# CmosTest20231115V3.net
KiCad netlist of a schematic drawn in Altium Designer
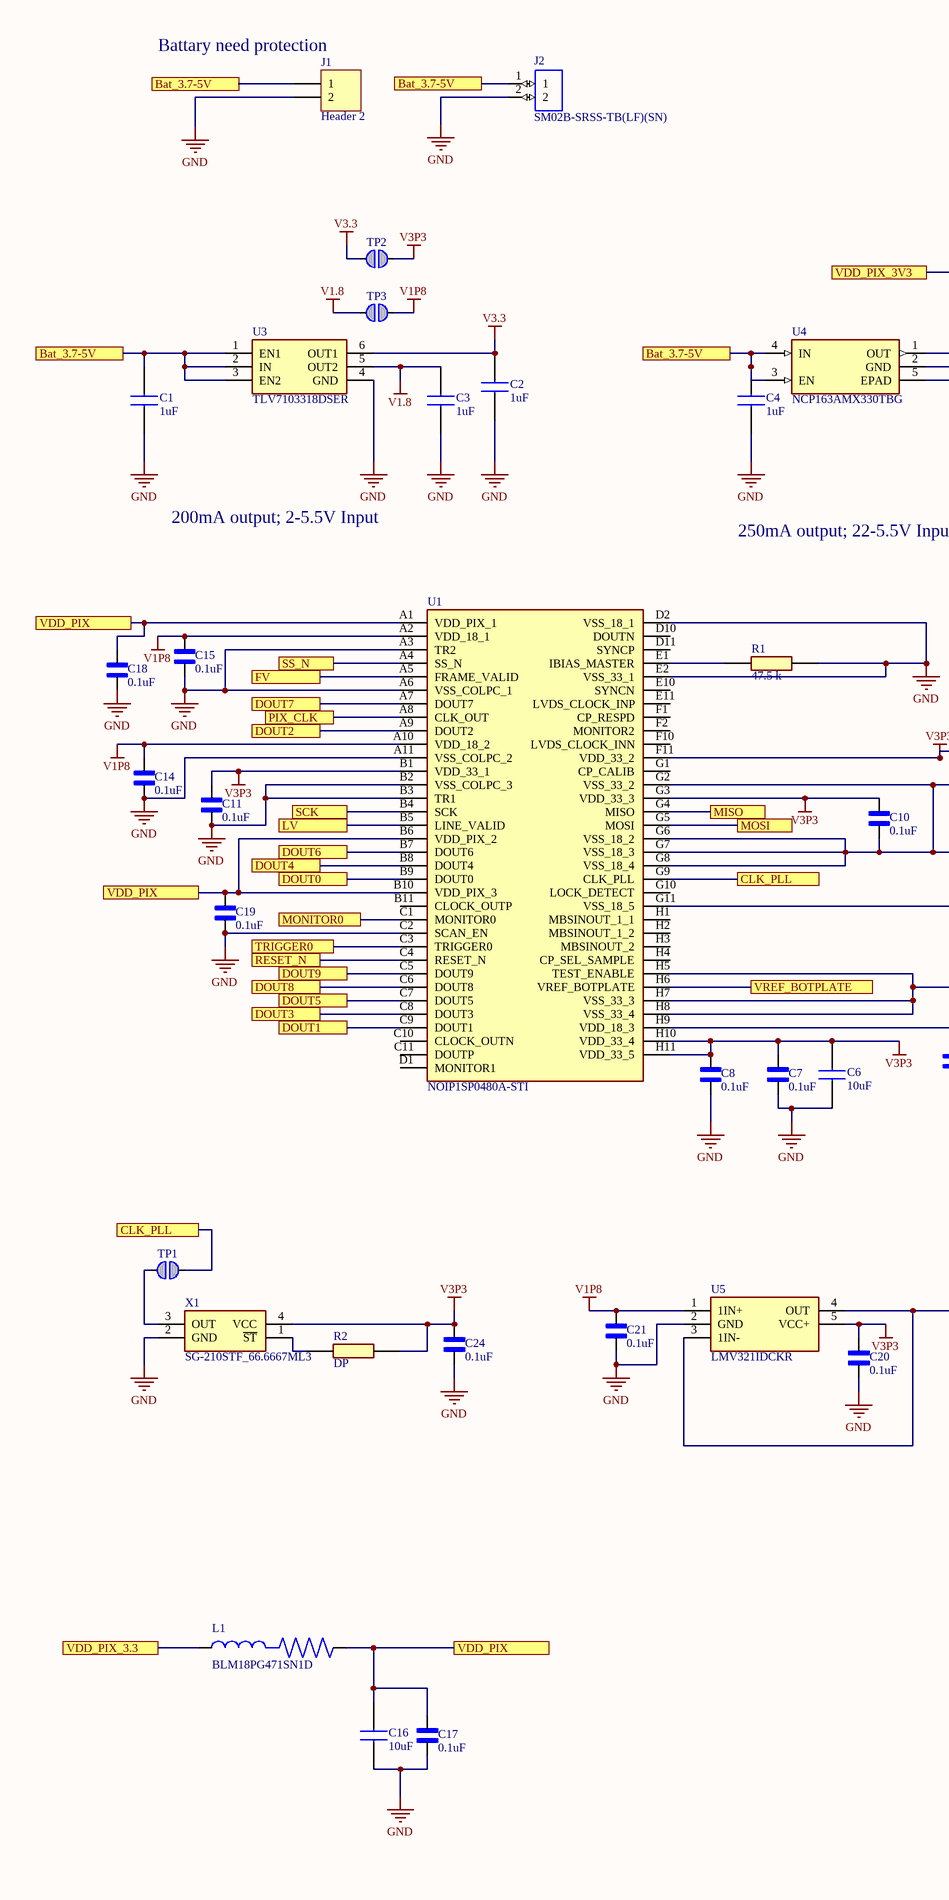
[diagram p0: CmosTest20231115V3.SchDoc, left]
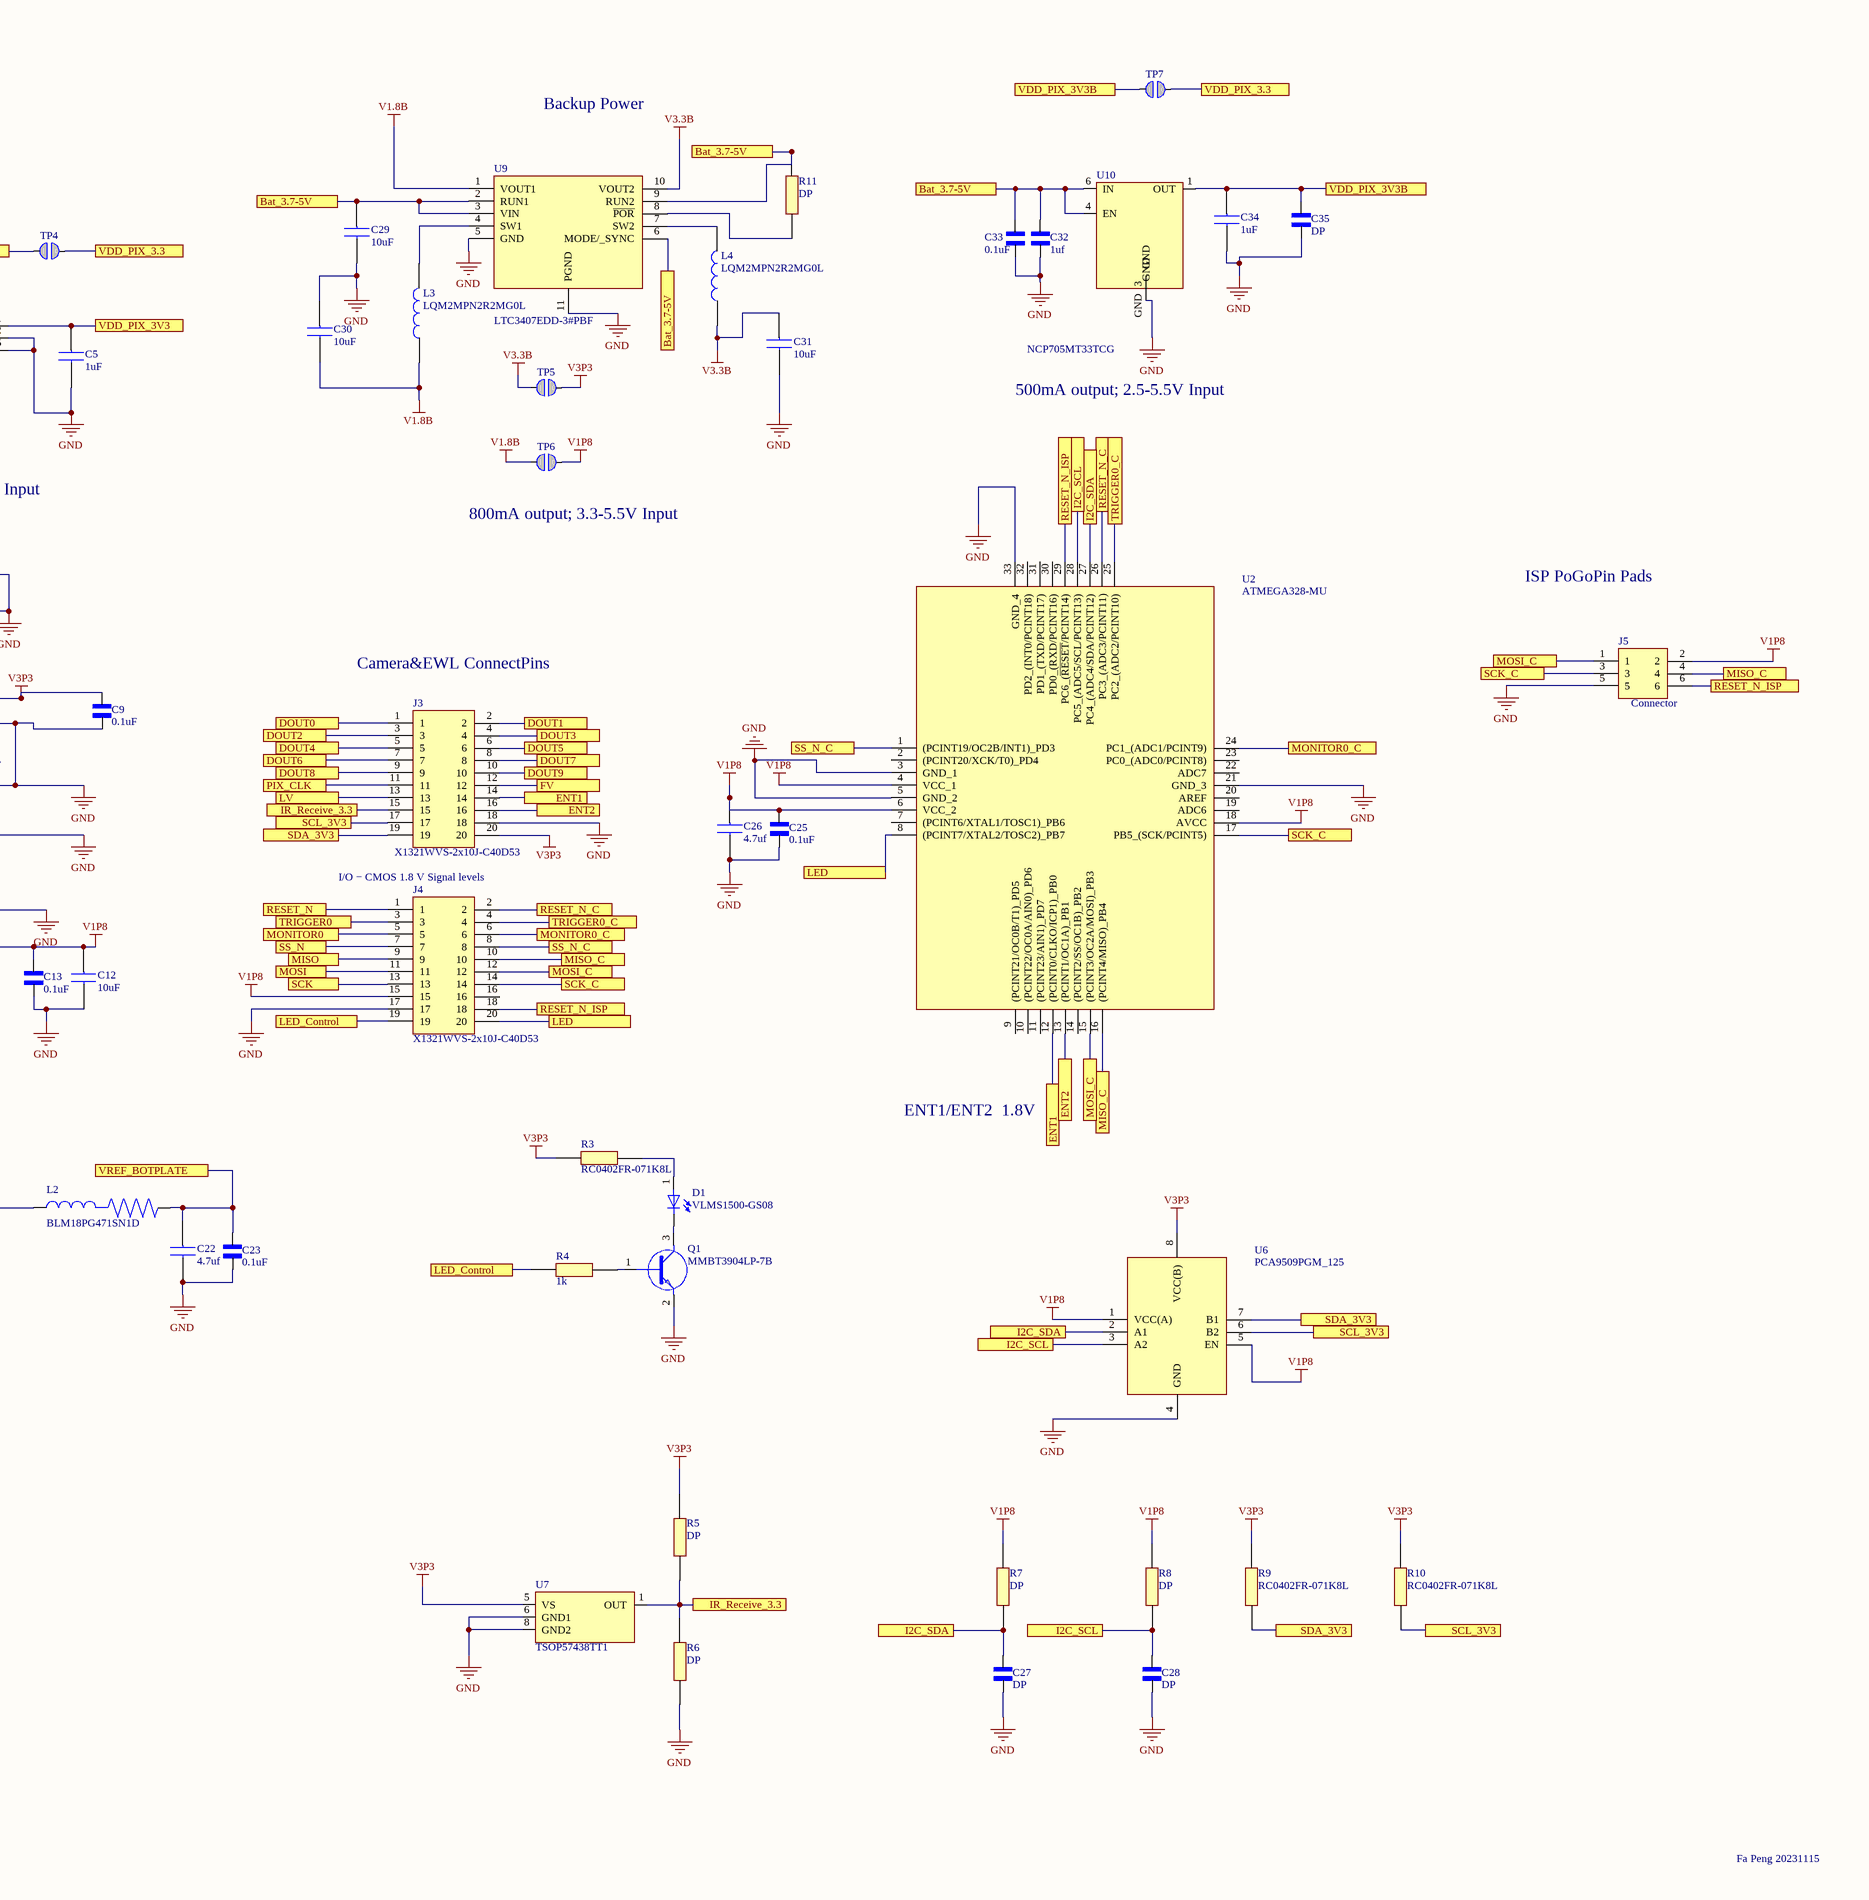
[diagram p1: CmosTest20231115V3.SchDoc, right]

(export (version "E")
  (design (tool "Eeschema 10.0.6"))
  (components
    (comp (ref "C1")
      (value "1uF")
      (footprint "CAPC1005X55N")
      (description "General purpose & High capacitance Class 2, X5R")
      (fields
        (field (name "MANUFACTURER_PART_NUMBER") "CC0402KRX5R6BB105")
        (field (name "MOUSER PART NUMBER") "603-CC402KRX5R6BB105")
      )
      (libsource (lib "CC0402KRX5R6BB105") (part "CC0402KRX5R6BB105"))
    )
    (comp (ref "C2")
      (value "1uF")
      (footprint "CAPC1005X55N")
      (description "CC0402KRX5R6BB105;General purpose & High capacitance Class 2, X5R")
      (fields
        (field (name "MANUFACTURER_PART_NUMBER") "CC0402KRX5R6BB105")
        (field (name "MOUSER PART NUMBER") "603-CC402KRX5R6BB105")
      )
      (libsource (lib "CC0402KRX5R6BB105") (part "CC0402KRX5R6BB105"))
    )
    (comp (ref "C3")
      (value "1uF")
      (footprint "CAPC1005X55N")
      (description "CC0402KRX5R6BB105; General purpose & High capacitance Class 2, X5R")
      (fields
        (field (name "MANUFACTURER_PART_NUMBER") "CC0402KRX5R6BB105")
        (field (name "MOUSER PART NUMBER") "603-CC402KRX5R6BB105")
      )
      (libsource (lib "CC0402KRX5R6BB105") (part "CC0402KRX5R6BB105"))
    )
    (comp (ref "C4")
      (value "1uF")
      (footprint "CAPC1005X55N")
      (description "General purpose & High capacitance Class 2, X5R")
      (fields
        (field (name "MANUFACTURER_PART_NUMBER") "CC0402KRX5R6BB105")
        (field (name "MOUSER PART NUMBER") "603-CC402KRX5R6BB105")
      )
      (libsource (lib "CC0402KRX5R6BB105") (part "CC0402KRX5R6BB105"))
    )
    (comp (ref "C5")
      (value "1uF")
      (footprint "CAPC1005X55N")
      (description "General purpose & High capacitance Class 2, X5R")
      (fields
        (field (name "MANUFACTURER_PART_NUMBER") "CC0402KRX5R6BB105")
        (field (name "MOUSER PART NUMBER") "603-CC402KRX5R6BB105")
      )
      (libsource (lib "CC0402KRX5R6BB105") (part "CC0402KRX5R6BB105"))
    )
    (comp (ref "C6")
      (value "10uF")
      (footprint "CAPC1005X56N")
      (description "0402ZD106MAT2A; Multilayer Ceramic Capacitors MLCC - SMD/SMT 10V 10uF X5R 0402 20% Tol")
      (fields
        (field (name "MANUFACTURER_PART_NUMBER") "0402ZD106MAT2A")
        (field (name "MOUSER PART NUMBER") "581-0402ZD106MAT2A")
      )
      (libsource (lib "0402ZD106MAT2A") (part "0402ZD106MAT2A"))
    )
    (comp (ref "C7")
      (value "0.1uF")
      (footprint "CAPC1005X55N")
      (description "SMD Capacitor X7R_EIA_ with Capacitance: 0.10uF Tol. 10%. Rated Voltage: 16Vdc;GRM155R71C104KA88D")
      (fields (field (name "MF") "Murata") (field (name "MP") "GRM155R71C104KA88D"))
      (libsource (lib "") (part "GRM155R71C104KA88D_1"))
    )
    (comp (ref "C8")
      (value "0.1uF")
      (footprint "CAPC1005X55N")
      (description "SMD Capacitor X7R_EIA_ with Capacitance: 0.10uF Tol. 10%. Rated Voltage: 16Vdc;GRM155R71C104KA88D")
      (fields (field (name "MF") "Murata") (field (name "MP") "GRM155R71C104KA88D"))
      (libsource (lib "") (part "GRM155R71C104KA88D_1"))
    )
    (comp (ref "C9")
      (value "0.1uF")
      (footprint "CAPC1005X55N")
      (description "SMD Capacitor X7R_EIA_ with Capacitance: 0.10uF Tol. 10%. Rated Voltage: 16Vdc;GRM155R71C104KA88D")
      (fields (field (name "MF") "Murata") (field (name "MP") "GRM155R71C104KA88D"))
      (libsource (lib "") (part "GRM155R71C104KA88D_1"))
    )
    (comp (ref "C10")
      (value "0.1uF")
      (footprint "CAPC1005X55N")
      (description "SMD Capacitor X7R_EIA_ with Capacitance: 0.10uF Tol. 10%. Rated Voltage: 16Vdc;GRM155R71C104KA88D")
      (fields (field (name "MF") "Murata") (field (name "MP") "GRM155R71C104KA88D"))
      (libsource (lib "") (part "GRM155R71C104KA88D_1"))
    )
    (comp (ref "C11")
      (value "0.1uF")
      (footprint "CAPC1005X55N")
      (description "SMD Capacitor X7R_EIA_ with Capacitance: 0.10uF Tol. 10%. Rated Voltage: 16Vdc;GRM155R71C104KA88D")
      (fields (field (name "MF") "Murata") (field (name "MP") "GRM155R71C104KA88D"))
      (libsource (lib "") (part "GRM155R71C104KA88D_1"))
    )
    (comp (ref "C12")
      (value "10uF")
      (footprint "CAPC1005X56N")
      (description "0402ZD106MAT2A; Multilayer Ceramic Capacitors MLCC - SMD/SMT 10V 10uF X5R 0402 20% Tol")
      (fields
        (field (name "MANUFACTURER_PART_NUMBER") "0402ZD106MAT2A")
        (field (name "MOUSER PART NUMBER") "581-0402ZD106MAT2A")
      )
      (libsource (lib "0402ZD106MAT2A") (part "0402ZD106MAT2A"))
    )
    (comp (ref "C13")
      (value "0.1uF")
      (footprint "CAPC1005X55N")
      (description "SMD Capacitor X7R_EIA_ with Capacitance: 0.10uF Tol. 10%. Rated Voltage: 16Vdc;GRM155R71C104KA88D")
      (fields (field (name "MF") "Murata") (field (name "MP") "GRM155R71C104KA88D"))
      (libsource (lib "") (part "GRM155R71C104KA88D_1"))
    )
    (comp (ref "C14")
      (value "0.1uF")
      (footprint "CAPC1005X55N")
      (description "SMD Capacitor X7R_EIA_ with Capacitance: 0.10uF Tol. 10%. Rated Voltage: 16Vdc;GRM155R71C104KA88D")
      (fields (field (name "MF") "Murata") (field (name "MP") "GRM155R71C104KA88D"))
      (libsource (lib "") (part "GRM155R71C104KA88D_1"))
    )
    (comp (ref "C15")
      (value "0.1uF")
      (footprint "CAPC1005X55N")
      (description "SMD Capacitor X7R_EIA_ with Capacitance: 0.10uF Tol. 10%. Rated Voltage: 16Vdc;GRM155R71C104KA88D")
      (fields (field (name "MF") "Murata") (field (name "MP") "GRM155R71C104KA88D"))
      (libsource (lib "") (part "GRM155R71C104KA88D_1"))
    )
    (comp (ref "C16")
      (value "10uF")
      (footprint "CAPC1005X56N")
      (description "0402ZD106MAT2A; Multilayer Ceramic Capacitors MLCC - SMD/SMT 10V 10uF X5R 0402 20% Tol")
      (fields
        (field (name "MANUFACTURER_PART_NUMBER") "0402ZD106MAT2A")
        (field (name "MOUSER PART NUMBER") "581-0402ZD106MAT2A")
      )
      (libsource (lib "0402ZD106MAT2A") (part "0402ZD106MAT2A"))
    )
    (comp (ref "C17")
      (value "0.1uF")
      (footprint "CAPC1005X55N")
      (description "SMD Capacitor X7R_EIA_ with Capacitance: 0.10uF Tol. 10%. Rated Voltage: 16Vdc;GRM155R71C104KA88D")
      (fields (field (name "MF") "Murata") (field (name "MP") "GRM155R71C104KA88D"))
      (libsource (lib "") (part "GRM155R71C104KA88D_1"))
    )
    (comp (ref "C18")
      (value "0.1uF")
      (footprint "CAPC1005X55N")
      (description "SMD Capacitor X7R_EIA_ with Capacitance: 0.10uF Tol. 10%. Rated Voltage: 16Vdc;GRM155R71C104KA88D")
      (fields (field (name "MF") "Murata") (field (name "MP") "GRM155R71C104KA88D"))
      (libsource (lib "") (part "GRM155R71C104KA88D_1"))
    )
    (comp (ref "C19")
      (value "0.1uF")
      (footprint "CAPC1005X55N")
      (description "SMD Capacitor X7R_EIA_ with Capacitance: 0.10uF Tol. 10%. Rated Voltage: 16Vdc;GRM155R71C104KA88D")
      (fields (field (name "MF") "Murata") (field (name "MP") "GRM155R71C104KA88D"))
      (libsource (lib "") (part "GRM155R71C104KA88D_1"))
    )
    (comp (ref "C20")
      (value "0.1uF")
      (footprint "CAPC1005X55N")
      (description "SMD Capacitor X7R_EIA_ with Capacitance: 0.10uF Tol. 10%. Rated Voltage: 16Vdc;GRM155R71C104KA88D")
      (fields (field (name "MF") "Murata") (field (name "MP") "GRM155R71C104KA88D"))
      (libsource (lib "") (part "GRM155R71C104KA88D_1"))
    )
    (comp (ref "C21")
      (value "0.1uF")
      (footprint "CAPC1005X55N")
      (description "SMD Capacitor X7R_EIA_ with Capacitance: 0.10uF Tol. 10%. Rated Voltage: 16Vdc;GRM155R71C104KA88D")
      (fields (field (name "MF") "Murata") (field (name "MP") "GRM155R71C104KA88D"))
      (libsource (lib "") (part "GRM155R71C104KA88D_1"))
    )
    (comp (ref "C22")
      (value "4.7uf")
      (footprint "CAPC1005X56N")
      (description "0402ZD475KAT2A; Multilayer Ceramic Capacitors MLCC - SMD/SMT 10V 4.7uF 0402 10% CX5R")
      (fields
        (field (name "MANUFACTURER_PART_NUMBER") "0402ZD475KAT2A")
        (field (name "MOUSER PART NUMBER") "581-0402ZD475KAT2A")
      )
      (libsource (lib "0402ZD475KAT2A") (part "0402ZD475KAT2A"))
    )
    (comp (ref "C23")
      (value "0.1uF")
      (footprint "CAPC1005X55N")
      (description "SMD Capacitor X7R_EIA_ with Capacitance: 0.10uF Tol. 10%. Rated Voltage: 16Vdc;GRM155R71C104KA88D")
      (fields (field (name "MF") "Murata") (field (name "MP") "GRM155R71C104KA88D"))
      (libsource (lib "") (part "GRM155R71C104KA88D_1"))
    )
    (comp (ref "C24")
      (value "0.1uF")
      (footprint "CAPC1005X55N")
      (description "SMD Capacitor X7R_EIA_ with Capacitance: 0.10uF Tol. 10%. Rated Voltage: 16Vdc;GRM155R71C104KA88D")
      (fields (field (name "MF") "Murata") (field (name "MP") "GRM155R71C104KA88D"))
      (libsource (lib "") (part "GRM155R71C104KA88D_1"))
    )
    (comp (ref "C25")
      (value "0.1uF")
      (footprint "CAPC1005X55N")
      (description "SMD Capacitor X7R_EIA_ with Capacitance: 0.10uF Tol. 10%. Rated Voltage: 16Vdc;GRM155R71C104KA88D")
      (fields (field (name "MF") "Murata") (field (name "MP") "GRM155R71C104KA88D"))
      (libsource (lib "") (part "GRM155R71C104KA88D_1"))
    )
    (comp (ref "C26")
      (value "4.7uf")
      (footprint "CAPC1005X56N")
      (description "0402ZD475KAT2A; Multilayer Ceramic Capacitors MLCC - SMD/SMT 10V 4.7uF 0402 10% CX5R")
      (fields
        (field (name "MANUFACTURER_PART_NUMBER") "0402ZD475KAT2A")
        (field (name "MOUSER PART NUMBER") "581-0402ZD475KAT2A")
      )
      (libsource (lib "0402ZD475KAT2A") (part "0402ZD475KAT2A"))
    )
    (comp (ref "C27")
      (value "DP")
      (footprint "CAPC1005X55N")
      (description "SMD Capacitor X7R_EIA_ with Capacitance: 0.10uF Tol. 10%. Rated Voltage: 16Vdc;GRM155R71C104KA88D")
      (fields (field (name "MF") "Murata") (field (name "MP") "GRM155R71C104KA88D"))
      (libsource (lib "") (part "GRM155R71C104KA88D_1"))
    )
    (comp (ref "C28")
      (value "DP")
      (footprint "CAPC1005X55N")
      (description "SMD Capacitor X7R_EIA_ with Capacitance: 0.10uF Tol. 10%. Rated Voltage: 16Vdc;GRM155R71C104KA88D")
      (fields (field (name "MF") "Murata") (field (name "MP") "GRM155R71C104KA88D"))
      (libsource (lib "") (part "GRM155R71C104KA88D_1"))
    )
    (comp (ref "C29")
      (value "10uF")
      (footprint "CAPC1005X56N")
      (description "0402ZD106MAT2A; Multilayer Ceramic Capacitors MLCC - SMD/SMT 10V 10uF X5R 0402 20% Tol")
      (fields
        (field (name "MANUFACTURER_PART_NUMBER") "0402ZD106MAT2A")
        (field (name "MOUSER PART NUMBER") "581-0402ZD106MAT2A")
      )
      (libsource (lib "0402ZD106MAT2A") (part "0402ZD106MAT2A"))
    )
    (comp (ref "C30")
      (value "10uF")
      (footprint "CAPC1005X56N")
      (description "0402ZD106MAT2A; Multilayer Ceramic Capacitors MLCC - SMD/SMT 10V 10uF X5R 0402 20% Tol")
      (fields
        (field (name "MANUFACTURER_PART_NUMBER") "0402ZD106MAT2A")
        (field (name "MOUSER PART NUMBER") "581-0402ZD106MAT2A")
      )
      (libsource (lib "0402ZD106MAT2A") (part "0402ZD106MAT2A"))
    )
    (comp (ref "C31")
      (value "10uF")
      (footprint "CAPC1005X56N")
      (description "0402ZD106MAT2A; Multilayer Ceramic Capacitors MLCC - SMD/SMT 10V 10uF X5R 0402 20% Tol")
      (fields
        (field (name "MANUFACTURER_PART_NUMBER") "0402ZD106MAT2A")
        (field (name "MOUSER PART NUMBER") "581-0402ZD106MAT2A")
      )
      (libsource (lib "0402ZD106MAT2A") (part "0402ZD106MAT2A"))
    )
    (comp (ref "C32")
      (value "1uf")
      (footprint "CAPC1005X55N")
      (description "SMD Capacitor X7R_EIA_ with Capacitance: 0.10uF Tol. 10%. Rated Voltage: 16Vdc")
      (fields (field (name "MF") "Murata") (field (name "MP") "GRM155R71C104KA88D"))
      (libsource (lib "GRM155R71C104KA88D 0.1uf 0402in") (part "GRM155R71C104KA88D"))
    )
    (comp (ref "C33")
      (value "0.1uF")
      (footprint "CAPC1005X55N")
      (description "SMD Capacitor X7R_EIA_ with Capacitance: 0.10uF Tol. 10%. Rated Voltage: 16Vdc")
      (fields (field (name "MF") "Murata") (field (name "MP") "GRM155R71C104KA88D"))
      (libsource (lib "") (part "GRM155R71C104KA88D_1"))
    )
    (comp (ref "C34")
      (value "1uF")
      (footprint "CAPC1005X55N")
      (description "General purpose & High capacitance Class 2, X5R")
      (fields
        (field (name "MANUFACTURER_PART_NUMBER") "CC0402KRX5R6BB105")
        (field (name "MOUSER PART NUMBER") "603-CC402KRX5R6BB105")
      )
      (libsource (lib "CC0402KRX5R6BB105") (part "CC0402KRX5R6BB105"))
    )
    (comp (ref "C35")
      (value "DP")
      (footprint "CAPC1005X55N")
      (description "SMD Capacitor X7R_EIA_ with Capacitance: 0.10uF Tol. 10%. Rated Voltage: 16Vdc")
      (fields (field (name "MF") "Murata") (field (name "MP") "GRM155R71C104KA88D"))
      (libsource (lib "") (part "GRM155R71C104KA88D_1"))
    )
    (comp (ref "D1")
      (value "VLMS1500-GS08")
      (footprint "RESC1005X40N")
      (description "Super red 631nm LED Indication - Discrete 2V 0402 _1005 Metric_")
      (fields (field (name "MF") "Vishay") (field (name "MP") "VLMG1500-GS08"))
      (libsource (lib "VLMG1500-GS08") (part "VLMG1500-GS08"))
    )
    (comp (ref "J1")
      (value "Header 2")
      (footprint "Head2_pad")
      (description "Header, 2-Pin")
      (fields (field (name "PUBLISHER") "Altium Limited"))
      (libsource (lib "Miscellaneous Connectors") (part "Header 2"))
    )
    (comp (ref "J2")
      (value "SM02B-SRSS-TB(LF)(SN)")
      (footprint "SM02B-SRSS-TB(LF)(SN)")
      (description "Connector Header Surface Mount, Right Angle 2 position 0.039 _1.00mm_")
      (fields (field (name "MP") "SM02B-SRSS-TB_LF__SN_") (field (name "MF") "JST Sales"))
      (libsource (lib "SM02B-SRSS-TB_LF__SN_") (part "SM02B-SRSS-TB(LF)(SN)"))
    )
    (comp (ref "J3")
      (value "X1321WVS-2x10J-C40D53")
      (footprint "62332021021")
      (fields
        (field (name "MANUFACTURER_PART_NUMBER") "62332021021")
        (field (name "MOUSER PART NUMBER") "710-62332021021")
      )
      (libsource (lib "62332021021") (part "62332021021"))
    )
    (comp (ref "J4")
      (value "X1321WVS-2x10J-C40D53")
      (footprint "62332021021")
      (fields
        (field (name "MANUFACTURER_PART_NUMBER") "62332021021")
        (field (name "MOUSER PART NUMBER") "710-62332021021")
      )
      (libsource (lib "62332021021") (part "62332021021"))
    )
    (comp (ref "J5") (value "Component_1") (libsource (lib "Connector2X3") (part "Component_1")))
    (comp (ref "L1")
      (value "BLM18PG471SN1D")
      (footprint "BEADC1608X95N")
      (description "470 Ohms @ 100MHz 1 Power Line Ferrite Bead 0603 _1608 Metric_ 1A 200mOhm")
      (fields (field (name "MF") "Murata") (field (name "DIGI-KEY_PART_NUMBER") "490-5223-1-ND"))
      (libsource (lib "BLM18PG471SN1D") (part "BLM18PG471SN1D"))
    )
    (comp (ref "L2")
      (value "BLM18PG471SN1D")
      (footprint "BEADC1608X95N")
      (description "470 Ohms @ 100MHz 1 Power Line Ferrite Bead 0603 _1608 Metric_ 1A 200mOhm")
      (fields (field (name "MF") "Murata") (field (name "DIGI-KEY_PART_NUMBER") "490-5223-1-ND"))
      (libsource (lib "BLM18PG471SN1D") (part "BLM18PG471SN1D"))
    )
    (comp (ref "L3")
      (value "LQM2MPN2R2MG0L")
      (footprint "LQM2MPN1R0NG0L")
      (description "LQM2MPN_G0 Series Inductor 2.2uH +/-20% 0806 (2016)")
      (fields (field (name "MOUSER PART NUMBER") "81-LQM2MPN2R2MG0L"))
      (libsource (lib "LQM2MPN2R2MG0L") (part "LQM2MPN2R2MG0L"))
    )
    (comp (ref "L4")
      (value "LQM2MPN2R2MG0L")
      (footprint "LQM2MPN1R0NG0L")
      (description "LQM2MPN_G0 Series Inductor 2.2uH +/-20% 0806 (2016)")
      (fields (field (name "MOUSER PART NUMBER") "81-LQM2MPN2R2MG0L"))
      (libsource (lib "LQM2MPN2R2MG0L") (part "LQM2MPN2R2MG0L"))
    )
    (comp (ref "Q1")
      (value "MMBT3904LP-7B")
      (footprint "MMBT3904LP7B")
      (fields (field (name "MOUSER PART NUMBER") "621-MMBT3904LP-7B"))
      (libsource (lib "MMBT3904LP-7B") (part "MMBT3904LP-7B"))
    )
    (comp (ref "R1")
      (value "47.5 k")
      (footprint "RESC1005X40N")
      (description "ERJ-2RKF4752X; Panasonic Surface Mount Fixed Resistor 47.5 k 0.1 W +/-100 ppm/C")
      (fields
        (field (name "MANUFACTURER_PART_NUMBER") "ERJ-2RKF4752X")
        (field (name "MOUSER PART NUMBER") "667-ERJ-2RKF4752X")
      )
      (libsource (lib "ERJ-2RKF4752X") (part "ERJ-2RKF4752X"))
    )
    (comp (ref "R2")
      (value "DP")
      (footprint "RESC1005X40N")
      (description "Don't place; RESISTOR, 0402")
      (fields
        (field (name "MANUFACTURER_PART_NUMBER") "RC0402FR-071K8L")
        (field (name "MOUSER PART NUMBER") "603-RC0402FR-071K8L")
      )
      (libsource (lib "") (part "RC0402FR-071K8L_3"))
    )
    (comp (ref "R3")
      (value "RC0402FR-071K8L")
      (footprint "RESC1005X40N")
      (description "RESISTOR, 0402 1.8K Ohms +/-1% 1/16 W")
      (fields (field (name "MOUSER PART NUMBER") "603-RC0402FR-071K8L"))
      (libsource (lib "") (part "RC0402FR-071K8L_2"))
    )
    (comp (ref "R4")
      (value "1k")
      (footprint "RESC1005X40N")
      (description "AC0402FR-071KL;  0402 1KΩ ±1% 1/16W ±100ppm/℃")
      (fields
        (field (name "MANUFACTURER_PART_NUMBER") "ERJ-2RKF4752X")
        (field (name "MOUSER PART NUMBER") "667-ERJ-2RKF4752X")
      )
      (libsource (lib "ERJ-2RKF4752X") (part "ERJ-2RKF4752X"))
    )
    (comp (ref "R5")
      (value "DP")
      (footprint "RESC1005X40N")
      (description "Don't place; RESISTOR, 0402")
      (fields
        (field (name "MANUFACTURER_PART_NUMBER") "RC0402FR-071K8L")
        (field (name "MOUSER PART NUMBER") "603-RC0402FR-071K8L")
      )
      (libsource (lib "RC0402FR-071K8L") (part "RC0402FR-071K8L"))
    )
    (comp (ref "R6")
      (value "DP")
      (footprint "RESC1005X40N")
      (description "Don't place; RESISTOR, 0402")
      (fields
        (field (name "MANUFACTURER_PART_NUMBER") "RC0402FR-071K8L")
        (field (name "MOUSER PART NUMBER") "603-RC0402FR-071K8L")
      )
      (libsource (lib "RC0402FR-071K8L") (part "RC0402FR-071K8L"))
    )
    (comp (ref "R7")
      (value "DP")
      (footprint "RESC1005X40N")
      (description "Don't place; RESISTOR, 0402")
      (fields
        (field (name "MANUFACTURER_PART_NUMBER") "RC0402FR-071K8L")
        (field (name "MOUSER PART NUMBER") "603-RC0402FR-071K8L")
      )
      (libsource (lib "RC0402FR-071K8L") (part "RC0402FR-071K8L"))
    )
    (comp (ref "R8")
      (value "DP")
      (footprint "RESC1005X40N")
      (description "Don't place; RESISTOR, 0402")
      (fields
        (field (name "MANUFACTURER_PART_NUMBER") "RC0402FR-071K8L")
        (field (name "MOUSER PART NUMBER") "603-RC0402FR-071K8L")
      )
      (libsource (lib "RC0402FR-071K8L") (part "RC0402FR-071K8L"))
    )
    (comp (ref "R9")
      (value "RC0402FR-071K8L")
      (footprint "RESC1005X40N")
      (description "RESISTOR, 0402 1.8K Ohms +/-1% 1/16 W")
      (fields (field (name "MOUSER PART NUMBER") "603-RC0402FR-071K8L"))
      (libsource (lib "") (part "RC0402FR-071K8L_1"))
    )
    (comp (ref "R10")
      (value "RC0402FR-071K8L")
      (footprint "RESC1005X40N")
      (description "RESISTOR, 0402 1.8K Ohms +/-1% 1/16 W")
      (fields (field (name "MOUSER PART NUMBER") "603-RC0402FR-071K8L"))
      (libsource (lib "") (part "RC0402FR-071K8L_1"))
    )
    (comp (ref "R11")
      (value "DP")
      (footprint "RESC1005X40N")
      (description "Don't place; RESISTOR, 0402")
      (fields
        (field (name "MANUFACTURER_PART_NUMBER") "RC0402FR-071K8L")
        (field (name "MOUSER PART NUMBER") "603-RC0402FR-071K8L")
      )
      (libsource (lib "") (part "RC0402FR-071K8L_1"))
    )
    (comp (ref "TP1")
      (value "Solderbridge")
      (footprint "Solderbridge")
      (fields (field (name "MANUFACTURER") "N.A.") (field (name "AUTHOR") "rsk"))
      (libsource (lib "400150_radio") (part "SOLDERBRIDGE"))
    )
    (comp (ref "TP2")
      (value "Solderbridge")
      (footprint "Solderbridge")
      (fields (field (name "MANUFACTURER") "N.A.") (field (name "AUTHOR") "rsk"))
      (libsource (lib "400150_radio") (part "SOLDERBRIDGE"))
    )
    (comp (ref "TP3")
      (value "Solderbridge")
      (footprint "Solderbridge")
      (fields (field (name "MANUFACTURER") "N.A.") (field (name "AUTHOR") "rsk"))
      (libsource (lib "400150_radio") (part "SOLDERBRIDGE"))
    )
    (comp (ref "TP4")
      (value "Solderbridge")
      (footprint "Solderbridge")
      (fields (field (name "MANUFACTURER") "N.A.") (field (name "AUTHOR") "rsk"))
      (libsource (lib "400150_radio") (part "SOLDERBRIDGE"))
    )
    (comp (ref "TP5")
      (value "Solderbridge")
      (footprint "Solderbridge")
      (fields (field (name "MANUFACTURER") "N.A.") (field (name "AUTHOR") "rsk"))
      (libsource (lib "400150_radio") (part "SOLDERBRIDGE"))
    )
    (comp (ref "TP6")
      (value "Solderbridge")
      (footprint "Solderbridge")
      (fields (field (name "MANUFACTURER") "N.A.") (field (name "AUTHOR") "rsk"))
      (libsource (lib "400150_radio") (part "SOLDERBRIDGE"))
    )
    (comp (ref "TP7")
      (value "Solderbridge")
      (footprint "Solderbridge")
      (fields (field (name "MANUFACTURER") "N.A.") (field (name "AUTHOR") "rsk"))
      (libsource (lib "400150_radio") (part "SOLDERBRIDGE"))
    )
    (comp (ref "U1")
      (value "NOIP1SP0480A-STI")
      (footprint "NOIP1SP0480ASTI")
      (description "Image Sensors PYTHON480 1/3.6 BW_ CRA")
      (fields (field (name "MOUSER PART NUMBER") "863-NOIP1SP0480A-STI"))
      (libsource (lib "NOIP1SP0480A-STI") (part "NOIP1SP0480A-STI"))
    )
    (comp (ref "U2")
      (value "ATMEGA328-MU")
      (footprint "QFN50P500X500X100-33N-D")
      (fields (field (name "MOUSER PART NUMBER") "556-ATMEGA328-MU"))
      (libsource (lib "ATMEGA328-MU") (part "ATMEGA328-MU"))
    )
    (comp (ref "U3")
      (value "TLV7103318DSER")
      (footprint "SON50P150X150X80-6N")
      (fields (field (name "MOUSER PART NUMBER") "595-TLV7103318DSER"))
      (libsource (lib "TLV7103318DSER") (part "TLV7103318DSER"))
    )
    (comp (ref "U4")
      (value "NCP163AMX330TBG")
      (footprint "REG_NCP114AMX330TBG")
      (description "NCP163(Vi 2.2-5..5V); Linear Voltage Regulator IC Positive Fixed 1 Output 250mA 4-UDFN _1.0x1.0_")
      (fields (field (name "MP") "NCP114AMX330TBG") (field (name "MF") "ON Semiconductor"))
      (libsource (lib "NCP114AMX330TBG") (part "NCP114AMX330TBG"))
    )
    (comp (ref "U5")
      (value "LMV321IDCKR")
      (footprint "SOT65P210X110-5N")
      (description "Single Low-Voltage Rail-to-Rail Output Operational Amplifier  see LMV321A for upgraded version")
      (fields (field (name "MOUSER PART NUMBER") "595-LMV321IDCKR"))
      (libsource (lib "LMV321IDCKR") (part "LMV321IDCKR"))
    )
    (comp (ref "U6")
      (value "PCA9509PGM_125")
      (footprint "PCA9509PGM125")
      (fields
        (field (name "MANUFACTURER_PART_NUMBER") "PCA9509PGM,125")
        (field (name "MOUSER PART NUMBER") "771-PCA9509PGM,125")
      )
      (libsource (lib "PCA9509PGM_125") (part "PCA9509PGM_125"))
    )
    (comp (ref "U7")
      (value "TSOP57438TT1")
      (footprint "TSOP572")
      (description "Remote Receiver Sensor, 38.0kHz 40m Surface Mount")
      (fields (field (name "MP") "TSOP57238TT1") (field (name "MF") "Vishay Semiconductor"))
      (libsource (lib "TSOP57238TT1") (part "TSOP57238TT1"))
    )
    (comp (ref "U9")
      (value "LTC3407EDD-3#PBF")
      (footprint "SON50P300X300X80-11N-D")
      (description "BUCK, SYNCH, DUAL, 0.8A, 2.25MHZ, 10MSOP")
      (fields (field (name "MOUSER PART NUMBER") "584-LTC3407EDD-3#PBF"))
      (libsource (lib "LTC3407EDD-3#PBF") (part "LTC3407EDD-3#PBF"))
    )
    (comp (ref "U10")
      (value "NCP705MT33TCG")
      (footprint "WDFN6")
      (fields (field (name "MP") "NCP705"))
      (libsource (lib "NCP705") (part "NCP705"))
    )
    (comp (ref "X1")
      (value "SG-210STF_66.6667ML3")
      (footprint "SG210STF625000ML3")
      (description "Standard Clock Oscillators 66.6666MHz 50ppm -40C +85C")
      (fields
        (field (name "MANUFACTURER_PART_NUMBER") "SG-210STF 62.5000ML3")
        (field (name "MOUSER PART NUMBER") "732-SG210STF62.500L3")
      )
      (libsource (lib "SG-210STF_62.5000ML3") (part "SG-210STF_62.5000ML3"))
    )
  )
  (nets
    (net (code "1") (name "/Bat_3.7-5V") (class "Default")
      (node (ref "C1") (pin "2") (pinfunction "2_2") (pintype "passive"))
      (node (ref "C29") (pin "2") (pinfunction "2_2") (pintype "passive"))
      (node (ref "C32") (pin "2") (pinfunction "2_2") (pintype "passive"))
      (node (ref "C33") (pin "1") (pinfunction "1_1") (pintype "passive"))
      (node (ref "C4") (pin "2") (pinfunction "2_2") (pintype "passive"))
      (node (ref "J1") (pin "1") (pinfunction "1_1") (pintype "passive"))
      (node (ref "J2") (pin "1") (pinfunction "1_1") (pintype "bidirectional"))
      (node (ref "R11") (pin "2") (pinfunction "2_2") (pintype "passive"))
      (node (ref "U10") (pin "4") (pinfunction "EN_4") (pintype "bidirectional"))
      (node (ref "U10") (pin "6") (pinfunction "IN_6") (pintype "bidirectional"))
      (node (ref "U3") (pin "1") (pinfunction "EN1_1") (pintype "passive"))
      (node (ref "U3") (pin "2") (pinfunction "IN_2") (pintype "passive"))
      (node (ref "U3") (pin "3") (pinfunction "EN2_3") (pintype "passive"))
      (node (ref "U4") (pin "3") (pinfunction "EN_3") (pintype "input"))
      (node (ref "U4") (pin "4") (pinfunction "IN_4") (pintype "input"))
      (node (ref "U9") (pin "2") (pinfunction "RUN1_2") (pintype "passive"))
      (node (ref "U9") (pin "3") (pinfunction "VIN_3") (pintype "passive"))
      (node (ref "U9") (pin "6") (pinfunction "MODE/_SYNC_6") (pintype "passive"))
      (node (ref "U9") (pin "9") (pinfunction "RUN2_9") (pintype "passive"))
    )
    (net (code "2") (name "/CLK_PLL") (class "Default")
      (node (ref "TP1") (pin "2") (pinfunction "1_2") (pintype "passive"))
      (node (ref "U1") (pin "G9") (pinfunction "CLK_PLL_G9") (pintype "passive"))
    )
    (net (code "3") (name "/DOUT0") (class "Default")
      (node (ref "J3") (pin "1") (pinfunction "1_1") (pintype "passive"))
      (node (ref "U1") (pin "B9") (pinfunction "DOUT0_B9") (pintype "passive"))
    )
    (net (code "4") (name "/DOUT1") (class "Default")
      (node (ref "J3") (pin "2") (pinfunction "2_2") (pintype "passive"))
      (node (ref "U1") (pin "C9") (pinfunction "DOUT1_C9") (pintype "passive"))
    )
    (net (code "5") (name "/DOUT2") (class "Default")
      (node (ref "J3") (pin "3") (pinfunction "3_3") (pintype "passive"))
      (node (ref "U1") (pin "A9") (pinfunction "DOUT2_A9") (pintype "passive"))
    )
    (net (code "6") (name "/DOUT3") (class "Default")
      (node (ref "J3") (pin "4") (pinfunction "4_4") (pintype "passive"))
      (node (ref "U1") (pin "C8") (pinfunction "DOUT3_C8") (pintype "passive"))
    )
    (net (code "7") (name "/DOUT4") (class "Default")
      (node (ref "J3") (pin "5") (pinfunction "5_5") (pintype "passive"))
      (node (ref "U1") (pin "B8") (pinfunction "DOUT4_B8") (pintype "passive"))
    )
    (net (code "8") (name "/DOUT5") (class "Default")
      (node (ref "J3") (pin "6") (pinfunction "6_6") (pintype "passive"))
      (node (ref "U1") (pin "C7") (pinfunction "DOUT5_C7") (pintype "passive"))
    )
    (net (code "9") (name "/DOUT6") (class "Default")
      (node (ref "J3") (pin "7") (pinfunction "7_7") (pintype "passive"))
      (node (ref "U1") (pin "B7") (pinfunction "DOUT6_B7") (pintype "passive"))
    )
    (net (code "10") (name "/DOUT7") (class "Default")
      (node (ref "J3") (pin "8") (pinfunction "8_8") (pintype "passive"))
      (node (ref "U1") (pin "A7") (pinfunction "DOUT7_A7") (pintype "passive"))
    )
    (net (code "11") (name "/DOUT8") (class "Default")
      (node (ref "J3") (pin "9") (pinfunction "9_9") (pintype "passive"))
      (node (ref "U1") (pin "C6") (pinfunction "DOUT8_C6") (pintype "passive"))
    )
    (net (code "12") (name "/DOUT9") (class "Default")
      (node (ref "J3") (pin "10") (pinfunction "10_10") (pintype "passive"))
      (node (ref "U1") (pin "C5") (pinfunction "DOUT9_C5") (pintype "passive"))
    )
    (net (code "13") (name "/ENT1") (class "Default")
      (node (ref "J3") (pin "14") (pinfunction "14_14") (pintype "passive"))
      (node (ref "U2") (pin "12") (pinfunction "(PCINT0/CLKO/ICP1)_PB0_12") (pintype "passive"))
    )
    (net (code "14") (name "/ENT2") (class "Default")
      (node (ref "J3") (pin "16") (pinfunction "16_16") (pintype "passive"))
      (node (ref "U2") (pin "13") (pinfunction "(PCINT1/OC1A)_PB1_13") (pintype "passive"))
    )
    (net (code "15") (name "/FV") (class "Default")
      (node (ref "J3") (pin "12") (pinfunction "12_12") (pintype "passive"))
      (node (ref "U1") (pin "A5") (pinfunction "FRAME_VALID_A5") (pintype "passive"))
    )
    (net (code "16") (name "/I2C_SCL") (class "Default")
      (node (ref "C28") (pin "1") (pinfunction "1_1") (pintype "passive"))
      (node (ref "R8") (pin "2") (pinfunction "2_2") (pintype "passive"))
      (node (ref "U2") (pin "28") (pinfunction "PC5_(ADC5/SCL/PCINT13)_28") (pintype "passive"))
      (node (ref "U6") (pin "3") (pinfunction "A2_3") (pintype "passive"))
    )
    (net (code "17") (name "/I2C_SDA") (class "Default")
      (node (ref "C27") (pin "1") (pinfunction "1_1") (pintype "passive"))
      (node (ref "R7") (pin "2") (pinfunction "2_2") (pintype "passive"))
      (node (ref "U2") (pin "27") (pinfunction "PC4_(ADC4/SDA/PCINT12)_27") (pintype "passive"))
      (node (ref "U6") (pin "2") (pinfunction "A1_2") (pintype "passive"))
    )
    (net (code "18") (name "/IR_Receive_3.3") (class "Default")
      (node (ref "J3") (pin "15") (pinfunction "15_15") (pintype "passive"))
      (node (ref "R5") (pin "2") (pinfunction "2_2") (pintype "passive"))
      (node (ref "R6") (pin "1") (pinfunction "1_1") (pintype "passive"))
      (node (ref "U7") (pin "1") (pinfunction "OUT_1") (pintype "bidirectional"))
    )
    (net (code "19") (name "/LED") (class "Default")
      (node (ref "J4") (pin "20") (pinfunction "20_20") (pintype "passive"))
      (node (ref "U2") (pin "8") (pinfunction "(PCINT7/XTAL2/TOSC2)_PB7_8") (pintype "passive"))
    )
    (net (code "20") (name "/LED_Control") (class "Default")
      (node (ref "J4") (pin "19") (pinfunction "19_19") (pintype "passive"))
      (node (ref "R4") (pin "1") (pinfunction "1_1") (pintype "passive"))
    )
    (net (code "21") (name "/LV") (class "Default")
      (node (ref "J3") (pin "13") (pinfunction "13_13") (pintype "passive"))
      (node (ref "U1") (pin "B5") (pinfunction "LINE_VALID_B5") (pintype "passive"))
    )
    (net (code "22") (name "/MISO") (class "Default")
      (node (ref "J4") (pin "9") (pinfunction "9_9") (pintype "passive"))
      (node (ref "U1") (pin "G4") (pinfunction "MISO_G4") (pintype "passive"))
    )
    (net (code "23") (name "/MISO_C") (class "Default")
      (node (ref "J4") (pin "10") (pinfunction "10_10") (pintype "passive"))
      (node (ref "J5") (pin "4") (pinfunction "4_4") (pintype "passive"))
      (node (ref "U2") (pin "16") (pinfunction "(PCINT4/MISO)_PB4_16") (pintype "passive"))
    )
    (net (code "24") (name "/MONITOR0") (class "Default")
      (node (ref "J4") (pin "5") (pinfunction "5_5") (pintype "passive"))
      (node (ref "U1") (pin "C1") (pinfunction "MONITOR0_C1") (pintype "passive"))
    )
    (net (code "25") (name "/MONITOR0_C") (class "Default")
      (node (ref "J4") (pin "6") (pinfunction "6_6") (pintype "passive"))
      (node (ref "U2") (pin "24") (pinfunction "PC1_(ADC1/PCINT9)_24") (pintype "passive"))
    )
    (net (code "26") (name "/MOSI") (class "Default")
      (node (ref "J4") (pin "11") (pinfunction "11_11") (pintype "passive"))
      (node (ref "U1") (pin "G5") (pinfunction "MOSI_G5") (pintype "passive"))
    )
    (net (code "27") (name "/MOSI_C") (class "Default")
      (node (ref "J4") (pin "12") (pinfunction "12_12") (pintype "passive"))
      (node (ref "J5") (pin "1") (pinfunction "1_1") (pintype "passive"))
      (node (ref "U2") (pin "15") (pinfunction "(PCINT3/OC2A/MOSI)_PB3_15") (pintype "passive"))
    )
    (net (code "28") (name "/PIX_CLK") (class "Default")
      (node (ref "J3") (pin "11") (pinfunction "11_11") (pintype "passive"))
      (node (ref "U1") (pin "A8") (pinfunction "CLK_OUT_A8") (pintype "passive"))
    )
    (net (code "29") (name "/RESET_N") (class "Default")
      (node (ref "J4") (pin "1") (pinfunction "1_1") (pintype "passive"))
      (node (ref "U1") (pin "C4") (pinfunction "RESET_N_C4") (pintype "passive"))
    )
    (net (code "30") (name "/RESET_N_C") (class "Default")
      (node (ref "J4") (pin "2") (pinfunction "2_2") (pintype "passive"))
      (node (ref "U2") (pin "26") (pinfunction "PC3_(ADC3/PCINT11)_26") (pintype "passive"))
    )
    (net (code "31") (name "/RESET_N_ISP") (class "Default")
      (node (ref "J4") (pin "18") (pinfunction "18_18") (pintype "passive"))
      (node (ref "J5") (pin "6") (pinfunction "6_6") (pintype "passive"))
      (node (ref "U2") (pin "29") (pinfunction "PC6_(~{RESET}/PCINT14)_29") (pintype "passive"))
    )
    (net (code "32") (name "/SCK") (class "Default")
      (node (ref "J4") (pin "13") (pinfunction "13_13") (pintype "passive"))
      (node (ref "U1") (pin "B4") (pinfunction "SCK_B4") (pintype "passive"))
    )
    (net (code "33") (name "/SCK_C") (class "Default")
      (node (ref "J4") (pin "14") (pinfunction "14_14") (pintype "passive"))
      (node (ref "J5") (pin "3") (pinfunction "3_3") (pintype "passive"))
      (node (ref "U2") (pin "17") (pinfunction "PB5_(SCK/PCINT5)_17") (pintype "passive"))
    )
    (net (code "34") (name "/SCL_3V3") (class "Default")
      (node (ref "J3") (pin "17") (pinfunction "17_17") (pintype "passive"))
      (node (ref "R10") (pin "1") (pinfunction "1_1") (pintype "passive"))
      (node (ref "U6") (pin "6") (pinfunction "B2_6") (pintype "passive"))
    )
    (net (code "35") (name "/SDA_3V3") (class "Default")
      (node (ref "J3") (pin "19") (pinfunction "19_19") (pintype "passive"))
      (node (ref "R9") (pin "1") (pinfunction "1_1") (pintype "passive"))
      (node (ref "U6") (pin "7") (pinfunction "B1_7") (pintype "passive"))
    )
    (net (code "36") (name "/SS_N") (class "Default")
      (node (ref "J4") (pin "7") (pinfunction "7_7") (pintype "passive"))
      (node (ref "U1") (pin "A4") (pinfunction "SS_N_A4") (pintype "passive"))
    )
    (net (code "37") (name "/SS_N_C") (class "Default")
      (node (ref "J4") (pin "8") (pinfunction "8_8") (pintype "passive"))
      (node (ref "U2") (pin "1") (pinfunction "(PCINT19/OC2B/INT1)_PD3_1") (pintype "passive"))
    )
    (net (code "38") (name "/TRIGGER0") (class "Default")
      (node (ref "J4") (pin "3") (pinfunction "3_3") (pintype "passive"))
      (node (ref "U1") (pin "C3") (pinfunction "TRIGGER0_C3") (pintype "passive"))
    )
    (net (code "39") (name "/TRIGGER0_C") (class "Default")
      (node (ref "J4") (pin "4") (pinfunction "4_4") (pintype "passive"))
      (node (ref "U2") (pin "25") (pinfunction "PC2_(ADC2/PCINT10)_25") (pintype "passive"))
    )
    (net (code "40") (name "/VDD_PIX") (class "Default")
      (node (ref "C16") (pin "2") (pinfunction "2_2") (pintype "passive"))
      (node (ref "C17") (pin "1") (pinfunction "1_1") (pintype "passive"))
      (node (ref "C18") (pin "1") (pinfunction "1_1") (pintype "passive"))
      (node (ref "C19") (pin "1") (pinfunction "1_1") (pintype "passive"))
      (node (ref "L1") (pin "2") (pinfunction "2_2") (pintype "passive"))
      (node (ref "U1") (pin "A1") (pinfunction "VDD_PIX_1_A1") (pintype "passive"))
      (node (ref "U1") (pin "B10") (pinfunction "VDD_PIX_3_B10") (pintype "passive"))
      (node (ref "U1") (pin "B6") (pinfunction "VDD_PIX_2_B6") (pintype "passive"))
    )
    (net (code "41") (name "/VDD_PIX_3.3") (class "Default")
      (node (ref "L1") (pin "1") (pinfunction "1_1") (pintype "passive"))
      (node (ref "TP4") (pin "1") (pinfunction "0_1") (pintype "passive"))
      (node (ref "TP7") (pin "1") (pinfunction "0_1") (pintype "passive"))
    )
    (net (code "42") (name "/VDD_PIX_3V3") (class "Default")
      (node (ref "C5") (pin "2") (pinfunction "2_2") (pintype "passive"))
      (node (ref "TP4") (pin "2") (pinfunction "1_2") (pintype "passive"))
      (node (ref "U4") (pin "1") (pinfunction "OUT_1") (pintype "output"))
    )
    (net (code "43") (name "/VDD_PIX_3V3B") (class "Default")
      (node (ref "C34") (pin "2") (pinfunction "2_2") (pintype "passive"))
      (node (ref "C35") (pin "1") (pinfunction "1_1") (pintype "passive"))
      (node (ref "TP7") (pin "2") (pinfunction "1_2") (pintype "passive"))
      (node (ref "U10") (pin "1") (pinfunction "OUT_1") (pintype "bidirectional"))
    )
    (net (code "44") (name "/VREF_BOTPLATE") (class "Default")
      (node (ref "C22") (pin "2") (pinfunction "2_2") (pintype "passive"))
      (node (ref "C23") (pin "1") (pinfunction "1_1") (pintype "passive"))
      (node (ref "L2") (pin "2") (pinfunction "2_2") (pintype "passive"))
      (node (ref "U1") (pin "H6") (pinfunction "VREF_BOTPLATE_H6") (pintype "passive"))
    )
    (net (code "45") (name "GND") (class "Default")
      (node (ref "C1") (pin "1") (pinfunction "1_1") (pintype "passive"))
      (node (ref "C10") (pin "2") (pinfunction "2_2") (pintype "passive"))
      (node (ref "C11") (pin "2") (pinfunction "2_2") (pintype "passive"))
      (node (ref "C12") (pin "1") (pinfunction "1_1") (pintype "passive"))
      (node (ref "C13") (pin "2") (pinfunction "2_2") (pintype "passive"))
      (node (ref "C14") (pin "2") (pinfunction "2_2") (pintype "passive"))
      (node (ref "C15") (pin "2") (pinfunction "2_2") (pintype "passive"))
      (node (ref "C16") (pin "1") (pinfunction "1_1") (pintype "passive"))
      (node (ref "C17") (pin "2") (pinfunction "2_2") (pintype "passive"))
      (node (ref "C18") (pin "2") (pinfunction "2_2") (pintype "passive"))
      (node (ref "C19") (pin "2") (pinfunction "2_2") (pintype "passive"))
      (node (ref "C2") (pin "1") (pinfunction "1_1") (pintype "passive"))
      (node (ref "C20") (pin "2") (pinfunction "2_2") (pintype "passive"))
      (node (ref "C21") (pin "2") (pinfunction "2_2") (pintype "passive"))
      (node (ref "C22") (pin "1") (pinfunction "1_1") (pintype "passive"))
      (node (ref "C23") (pin "2") (pinfunction "2_2") (pintype "passive"))
      (node (ref "C24") (pin "2") (pinfunction "2_2") (pintype "passive"))
      (node (ref "C25") (pin "2") (pinfunction "2_2") (pintype "passive"))
      (node (ref "C26") (pin "1") (pinfunction "1_1") (pintype "passive"))
      (node (ref "C27") (pin "2") (pinfunction "2_2") (pintype "passive"))
      (node (ref "C28") (pin "2") (pinfunction "2_2") (pintype "passive"))
      (node (ref "C29") (pin "1") (pinfunction "1_1") (pintype "passive"))
      (node (ref "C3") (pin "1") (pinfunction "1_1") (pintype "passive"))
      (node (ref "C30") (pin "2") (pinfunction "2_2") (pintype "passive"))
      (node (ref "C31") (pin "1") (pinfunction "1_1") (pintype "passive"))
      (node (ref "C32") (pin "1") (pinfunction "1_1") (pintype "passive"))
      (node (ref "C33") (pin "2") (pinfunction "2_2") (pintype "passive"))
      (node (ref "C34") (pin "1") (pinfunction "1_1") (pintype "passive"))
      (node (ref "C35") (pin "2") (pinfunction "2_2") (pintype "passive"))
      (node (ref "C4") (pin "1") (pinfunction "1_1") (pintype "passive"))
      (node (ref "C5") (pin "1") (pinfunction "1_1") (pintype "passive"))
      (node (ref "C6") (pin "1") (pinfunction "1_1") (pintype "passive"))
      (node (ref "C7") (pin "2") (pinfunction "2_2") (pintype "passive"))
      (node (ref "C8") (pin "2") (pinfunction "2_2") (pintype "passive"))
      (node (ref "C9") (pin "2") (pinfunction "2_2") (pintype "passive"))
      (node (ref "J1") (pin "2") (pinfunction "2_2") (pintype "passive"))
      (node (ref "J2") (pin "2") (pinfunction "2_2") (pintype "bidirectional"))
      (node (ref "J3") (pin "18") (pinfunction "18_18") (pintype "passive"))
      (node (ref "J4") (pin "17") (pinfunction "17_17") (pintype "passive"))
      (node (ref "J5") (pin "5") (pinfunction "5_5") (pintype "passive"))
      (node (ref "Q1") (pin "2") (pinfunction "E_2") (pintype "passive"))
      (node (ref "R1") (pin "2") (pinfunction "2_2") (pintype "passive"))
      (node (ref "R6") (pin "2") (pinfunction "2_2") (pintype "passive"))
      (node (ref "U1") (pin "A11") (pinfunction "VSS_COLPC_2_A11") (pintype "passive"))
      (node (ref "U1") (pin "A3") (pinfunction "TR2_A3") (pintype "passive"))
      (node (ref "U1") (pin "A6") (pinfunction "VSS_COLPC_1_A6") (pintype "passive"))
      (node (ref "U1") (pin "B2") (pinfunction "VSS_COLPC_3_B2") (pintype "passive"))
      (node (ref "U1") (pin "B3") (pinfunction "TR1_B3") (pintype "passive"))
      (node (ref "U1") (pin "C2") (pinfunction "SCAN_EN_C2") (pintype "passive"))
      (node (ref "U1") (pin "D2") (pinfunction "VSS_18_1_D2") (pintype "passive"))
      (node (ref "U1") (pin "E2") (pinfunction "VSS_33_1_E2") (pintype "passive"))
      (node (ref "U1") (pin "G11") (pinfunction "VSS_18_5_G11") (pintype "passive"))
      (node (ref "U1") (pin "G2") (pinfunction "VSS_33_2_G2") (pintype "passive"))
      (node (ref "U1") (pin "G6") (pinfunction "VSS_18_2_G6") (pintype "passive"))
      (node (ref "U1") (pin "G7") (pinfunction "VSS_18_3_G7") (pintype "passive"))
      (node (ref "U1") (pin "G8") (pinfunction "VSS_18_4_G8") (pintype "passive"))
      (node (ref "U1") (pin "H5") (pinfunction "TEST_ENABLE_H5") (pintype "passive"))
      (node (ref "U1") (pin "H7") (pinfunction "VSS_33_3_H7") (pintype "passive"))
      (node (ref "U1") (pin "H8") (pinfunction "VSS_33_4_H8") (pintype "passive"))
      (node (ref "U10") (pin "GND") (pinfunction "GND_GND") (pintype "bidirectional"))
      (node (ref "U2") (pin "21") (pinfunction "GND_3_21") (pintype "passive"))
      (node (ref "U2") (pin "3") (pinfunction "GND_1_3") (pintype "passive"))
      (node (ref "U2") (pin "33") (pinfunction "GND_4_33") (pintype "passive"))
      (node (ref "U2") (pin "5") (pinfunction "GND_2_5") (pintype "passive"))
      (node (ref "U3") (pin "4") (pinfunction "GND_4") (pintype "passive"))
      (node (ref "U4") (pin "2") (pinfunction "GND_2") (pintype "power_in"))
      (node (ref "U4") (pin "5") (pinfunction "EPAD_5") (pintype "passive"))
      (node (ref "U5") (pin "2") (pinfunction "GND_2") (pintype "passive"))
      (node (ref "U6") (pin "4") (pinfunction "GND_4") (pintype "passive"))
      (node (ref "U7") (pin "6") (pinfunction "GND1_6") (pintype "bidirectional"))
      (node (ref "U7") (pin "8") (pinfunction "GND2_8") (pintype "bidirectional"))
      (node (ref "U9") (pin "11") (pinfunction "PGND_11") (pintype "passive"))
      (node (ref "U9") (pin "5") (pinfunction "GND_5") (pintype "passive"))
      (node (ref "X1") (pin "2") (pinfunction "GND_2") (pintype "passive"))
    )
    (net (code "46") (name "Net-(D1-Pad1)") (class "Default")
      (node (ref "D1") (pin "1") (pinfunction "1_1") (pintype "passive"))
      (node (ref "R3") (pin "2") (pinfunction "2_2") (pintype "passive"))
    )
    (net (code "47") (name "Net-(Q1-B)") (class "Default")
      (node (ref "Q1") (pin "1") (pinfunction "B_1") (pintype "passive"))
      (node (ref "R4") (pin "2") (pinfunction "2_2") (pintype "passive"))
    )
    (net (code "48") (name "Net-(Q1-C)") (class "Default")
      (node (ref "D1") (pin "2") (pinfunction "2_2") (pintype "passive"))
      (node (ref "Q1") (pin "3") (pinfunction "C_3") (pintype "passive"))
    )
    (net (code "49") (name "Net-(TP1-0)") (class "Default")
      (node (ref "TP1") (pin "1") (pinfunction "0_1") (pintype "passive"))
      (node (ref "X1") (pin "3") (pinfunction "OUT_3") (pintype "passive"))
    )
    (net (code "50") (name "Net-(U1-IBIAS_MASTER)") (class "Default")
      (node (ref "R1") (pin "1") (pinfunction "1_1") (pintype "passive"))
      (node (ref "U1") (pin "E1") (pinfunction "IBIAS_MASTER_E1") (pintype "passive"))
    )
    (net (code "51") (name "Net-(U5-1IN-)") (class "Default")
      (node (ref "L2") (pin "1") (pinfunction "1_1") (pintype "passive"))
      (node (ref "U5") (pin "3") (pinfunction "1IN-_3") (pintype "passive"))
      (node (ref "U5") (pin "4") (pinfunction "OUT_4") (pintype "passive"))
    )
    (net (code "52") (name "Net-(U9-SW1)") (class "Default")
      (node (ref "L3") (pin "2") (pinfunction "2_2") (pintype "passive"))
      (node (ref "U9") (pin "4") (pinfunction "SW1_4") (pintype "passive"))
    )
    (net (code "53") (name "Net-(U9-SW2)") (class "Default")
      (node (ref "L4") (pin "2") (pinfunction "2_2") (pintype "passive"))
      (node (ref "U9") (pin "7") (pinfunction "SW2_7") (pintype "passive"))
    )
    (net (code "54") (name "Net-(U9-~{POR})") (class "Default")
      (node (ref "R11") (pin "1") (pinfunction "1_1") (pintype "passive"))
      (node (ref "U9") (pin "8") (pinfunction "~{POR}_8") (pintype "passive"))
    )
    (net (code "55") (name "Net-(X1-~{ST})") (class "Default")
      (node (ref "R2") (pin "2") (pinfunction "2_2") (pintype "passive"))
      (node (ref "X1") (pin "1") (pinfunction "~{ST}_1") (pintype "passive"))
    )
    (net (code "56") (name "V1.8") (class "Default")
      (node (ref "C3") (pin "2") (pinfunction "2_2") (pintype "passive"))
      (node (ref "TP3") (pin "2") (pinfunction "1_2") (pintype "passive"))
      (node (ref "U3") (pin "5") (pinfunction "OUT2_5") (pintype "passive"))
    )
    (net (code "57") (name "V1.8B") (class "Default")
      (node (ref "C30") (pin "1") (pinfunction "1_1") (pintype "passive"))
      (node (ref "L3") (pin "1") (pinfunction "1_1") (pintype "passive"))
      (node (ref "TP6") (pin "2") (pinfunction "1_2") (pintype "passive"))
      (node (ref "U9") (pin "1") (pinfunction "VOUT1_1") (pintype "passive"))
    )
    (net (code "58") (name "V1P8") (class "Default")
      (node (ref "C12") (pin "2") (pinfunction "2_2") (pintype "passive"))
      (node (ref "C13") (pin "1") (pinfunction "1_1") (pintype "passive"))
      (node (ref "C14") (pin "1") (pinfunction "1_1") (pintype "passive"))
      (node (ref "C15") (pin "1") (pinfunction "1_1") (pintype "passive"))
      (node (ref "C21") (pin "1") (pinfunction "1_1") (pintype "passive"))
      (node (ref "C25") (pin "1") (pinfunction "1_1") (pintype "passive"))
      (node (ref "C26") (pin "2") (pinfunction "2_2") (pintype "passive"))
      (node (ref "J4") (pin "15") (pinfunction "15_15") (pintype "passive"))
      (node (ref "J5") (pin "2") (pinfunction "2_2") (pintype "passive"))
      (node (ref "R7") (pin "1") (pinfunction "1_1") (pintype "passive"))
      (node (ref "R8") (pin "1") (pinfunction "1_1") (pintype "passive"))
      (node (ref "TP3") (pin "1") (pinfunction "0_1") (pintype "passive"))
      (node (ref "TP6") (pin "1") (pinfunction "0_1") (pintype "passive"))
      (node (ref "U1") (pin "A10") (pinfunction "VDD_18_2_A10") (pintype "passive"))
      (node (ref "U1") (pin "A2") (pinfunction "VDD_18_1_A2") (pintype "passive"))
      (node (ref "U1") (pin "H9") (pinfunction "VDD_18_3_H9") (pintype "passive"))
      (node (ref "U2") (pin "18") (pinfunction "AVCC_18") (pintype "passive"))
      (node (ref "U2") (pin "4") (pinfunction "VCC_1_4") (pintype "passive"))
      (node (ref "U2") (pin "6") (pinfunction "VCC_2_6") (pintype "passive"))
      (node (ref "U5") (pin "1") (pinfunction "1IN+_1") (pintype "passive"))
      (node (ref "U6") (pin "1") (pinfunction "VCC(A)_1") (pintype "passive"))
      (node (ref "U6") (pin "5") (pinfunction "EN_5") (pintype "passive"))
    )
    (net (code "59") (name "V3.3") (class "Default")
      (node (ref "C2") (pin "2") (pinfunction "2_2") (pintype "passive"))
      (node (ref "TP2") (pin "2") (pinfunction "1_2") (pintype "passive"))
      (node (ref "U3") (pin "6") (pinfunction "OUT1_6") (pintype "passive"))
    )
    (net (code "60") (name "V3.3B") (class "Default")
      (node (ref "C31") (pin "2") (pinfunction "2_2") (pintype "passive"))
      (node (ref "L4") (pin "1") (pinfunction "1_1") (pintype "passive"))
      (node (ref "TP5") (pin "2") (pinfunction "1_2") (pintype "passive"))
      (node (ref "U9") (pin "10") (pinfunction "VOUT2_10") (pintype "passive"))
    )
    (net (code "61") (name "V3P3") (class "Default")
      (node (ref "C10") (pin "1") (pinfunction "1_1") (pintype "passive"))
      (node (ref "C11") (pin "1") (pinfunction "1_1") (pintype "passive"))
      (node (ref "C20") (pin "1") (pinfunction "1_1") (pintype "passive"))
      (node (ref "C24") (pin "1") (pinfunction "1_1") (pintype "passive"))
      (node (ref "C6") (pin "2") (pinfunction "2_2") (pintype "passive"))
      (node (ref "C7") (pin "1") (pinfunction "1_1") (pintype "passive"))
      (node (ref "C8") (pin "1") (pinfunction "1_1") (pintype "passive"))
      (node (ref "C9") (pin "1") (pinfunction "1_1") (pintype "passive"))
      (node (ref "J3") (pin "20") (pinfunction "20_20") (pintype "passive"))
      (node (ref "R10") (pin "2") (pinfunction "2_2") (pintype "passive"))
      (node (ref "R2") (pin "1") (pinfunction "1_1") (pintype "passive"))
      (node (ref "R3") (pin "1") (pinfunction "1_1") (pintype "passive"))
      (node (ref "R5") (pin "1") (pinfunction "1_1") (pintype "passive"))
      (node (ref "R9") (pin "2") (pinfunction "2_2") (pintype "passive"))
      (node (ref "TP2") (pin "1") (pinfunction "0_1") (pintype "passive"))
      (node (ref "TP5") (pin "1") (pinfunction "0_1") (pintype "passive"))
      (node (ref "U1") (pin "B1") (pinfunction "VDD_33_1_B1") (pintype "passive"))
      (node (ref "U1") (pin "F11") (pinfunction "VDD_33_2_F11") (pintype "passive"))
      (node (ref "U1") (pin "G3") (pinfunction "VDD_33_3_G3") (pintype "passive"))
      (node (ref "U1") (pin "H10") (pinfunction "VDD_33_4_H10") (pintype "passive"))
      (node (ref "U1") (pin "H11") (pinfunction "VDD_33_5_H11") (pintype "passive"))
      (node (ref "U5") (pin "5") (pinfunction "VCC+_5") (pintype "passive"))
      (node (ref "U6") (pin "8") (pinfunction "VCC(B)_8") (pintype "passive"))
      (node (ref "U7") (pin "5") (pinfunction "VS_5") (pintype "bidirectional"))
      (node (ref "X1") (pin "4") (pinfunction "VCC_4") (pintype "passive"))
    )
    (net (code "62") (name "unconnected-(J4-Pad16)") (class "Default")
      (node (ref "J4") (pin "16") (pinfunction "16_16") (pintype "passive"))
    )
    (net (code "63") (name "unconnected-(U1-CLOCK_OUTN-PadC10)") (class "Default")
      (node (ref "U1") (pin "C10") (pinfunction "CLOCK_OUTN_C10") (pintype "passive"))
    )
    (net (code "64") (name "unconnected-(U1-CLOCK_OUTP-PadB11)") (class "Default")
      (node (ref "U1") (pin "B11") (pinfunction "CLOCK_OUTP_B11") (pintype "passive"))
    )
    (net (code "65") (name "unconnected-(U1-CP_CALIB-PadG1)") (class "Default")
      (node (ref "U1") (pin "G1") (pinfunction "CP_CALIB_G1") (pintype "passive"))
    )
    (net (code "66") (name "unconnected-(U1-CP_RESPD-PadF1)") (class "Default")
      (node (ref "U1") (pin "F1") (pinfunction "CP_RESPD_F1") (pintype "passive"))
    )
    (net (code "67") (name "unconnected-(U1-CP_SEL_SAMPLE-PadH4)") (class "Default")
      (node (ref "U1") (pin "H4") (pinfunction "CP_SEL_SAMPLE_H4") (pintype "passive"))
    )
    (net (code "68") (name "unconnected-(U1-DOUTN-PadD10)") (class "Default")
      (node (ref "U1") (pin "D10") (pinfunction "DOUTN_D10") (pintype "passive"))
    )
    (net (code "69") (name "unconnected-(U1-DOUTP-PadC11)") (class "Default")
      (node (ref "U1") (pin "C11") (pinfunction "DOUTP_C11") (pintype "passive"))
    )
    (net (code "70") (name "unconnected-(U1-LOCK_DETECT-PadG10)") (class "Default")
      (node (ref "U1") (pin "G10") (pinfunction "LOCK_DETECT_G10") (pintype "passive"))
    )
    (net (code "71") (name "unconnected-(U1-LVDS_CLOCK_INN-PadF10)") (class "Default")
      (node (ref "U1") (pin "F10") (pinfunction "LVDS_CLOCK_INN_F10") (pintype "passive"))
    )
    (net (code "72") (name "unconnected-(U1-LVDS_CLOCK_INP-PadE11)") (class "Default")
      (node (ref "U1") (pin "E11") (pinfunction "LVDS_CLOCK_INP_E11") (pintype "passive"))
    )
    (net (code "73") (name "unconnected-(U1-MBSINOUT_1_1-PadH1)") (class "Default")
      (node (ref "U1") (pin "H1") (pinfunction "MBSINOUT_1_1_H1") (pintype "passive"))
    )
    (net (code "74") (name "unconnected-(U1-MBSINOUT_1_2-PadH2)") (class "Default")
      (node (ref "U1") (pin "H2") (pinfunction "MBSINOUT_1_2_H2") (pintype "passive"))
    )
    (net (code "75") (name "unconnected-(U1-MBSINOUT_2-PadH3)") (class "Default")
      (node (ref "U1") (pin "H3") (pinfunction "MBSINOUT_2_H3") (pintype "passive"))
    )
    (net (code "76") (name "unconnected-(U1-MONITOR1-PadD1)") (class "Default")
      (node (ref "U1") (pin "D1") (pinfunction "MONITOR1_D1") (pintype "passive"))
    )
    (net (code "77") (name "unconnected-(U1-MONITOR2-PadF2)") (class "Default")
      (node (ref "U1") (pin "F2") (pinfunction "MONITOR2_F2") (pintype "passive"))
    )
    (net (code "78") (name "unconnected-(U1-SYNCN-PadE10)") (class "Default")
      (node (ref "U1") (pin "E10") (pinfunction "SYNCN_E10") (pintype "passive"))
    )
    (net (code "79") (name "unconnected-(U1-SYNCP-PadD11)") (class "Default")
      (node (ref "U1") (pin "D11") (pinfunction "SYNCP_D11") (pintype "passive"))
    )
    (net (code "80") (name "unconnected-(U2-(PCINT2{slash}SS{slash}OC1B)_PB2-Pad14)") (class "Default")
      (node (ref "U2") (pin "14") (pinfunction "(PCINT2/SS/OC1B)_PB2_14") (pintype "passive"))
    )
    (net (code "81") (name "unconnected-(U2-(PCINT6{slash}XTAL1{slash}TOSC1)_PB6-Pad7)") (class "Default")
      (node (ref "U2") (pin "7") (pinfunction "(PCINT6/XTAL1/TOSC1)_PB6_7") (pintype "passive"))
    )
    (net (code "82") (name "unconnected-(U2-(PCINT20{slash}XCK{slash}T0)_PD4-Pad2)") (class "Default")
      (node (ref "U2") (pin "2") (pinfunction "(PCINT20/XCK/T0)_PD4_2") (pintype "passive"))
    )
    (net (code "83") (name "unconnected-(U2-(PCINT21{slash}OC0B{slash}T1)_PD5-Pad9)") (class "Default")
      (node (ref "U2") (pin "9") (pinfunction "(PCINT21/OC0B/T1)_PD5_9") (pintype "passive"))
    )
    (net (code "84") (name "unconnected-(U2-(PCINT22{slash}OC0A{slash}AIN0)_PD6-Pad10)") (class "Default")
      (node (ref "U2") (pin "10") (pinfunction "(PCINT22/OC0A/AIN0)_PD6_10") (pintype "passive"))
    )
    (net (code "85") (name "unconnected-(U2-(PCINT23{slash}AIN1)_PD7-Pad11)") (class "Default")
      (node (ref "U2") (pin "11") (pinfunction "(PCINT23/AIN1)_PD7_11") (pintype "passive"))
    )
    (net (code "86") (name "unconnected-(U2-ADC6-Pad19)") (class "Default")
      (node (ref "U2") (pin "19") (pinfunction "ADC6_19") (pintype "passive"))
    )
    (net (code "87") (name "unconnected-(U2-ADC7-Pad22)") (class "Default")
      (node (ref "U2") (pin "22") (pinfunction "ADC7_22") (pintype "passive"))
    )
    (net (code "88") (name "unconnected-(U2-AREF-Pad20)") (class "Default")
      (node (ref "U2") (pin "20") (pinfunction "AREF_20") (pintype "passive"))
    )
    (net (code "89") (name "unconnected-(U2-PC0_(ADC0{slash}PCINT8)-Pad23)") (class "Default")
      (node (ref "U2") (pin "23") (pinfunction "PC0_(ADC0/PCINT8)_23") (pintype "passive"))
    )
    (net (code "90") (name "unconnected-(U2-PD0_(RXD{slash}PCINT16)-Pad30)") (class "Default")
      (node (ref "U2") (pin "30") (pinfunction "PD0_(RXD/PCINT16)_30") (pintype "passive"))
    )
    (net (code "91") (name "unconnected-(U2-PD1_(TXD{slash}PCINT17)-Pad31)") (class "Default")
      (node (ref "U2") (pin "31") (pinfunction "PD1_(TXD/PCINT17)_31") (pintype "passive"))
    )
    (net (code "92") (name "unconnected-(U2-PD2_(INT0{slash}PCINT18)-Pad32)") (class "Default")
      (node (ref "U2") (pin "32") (pinfunction "PD2_(INT0/PCINT18)_32") (pintype "passive"))
    )
    (net (code "93") (name "unconnected-(U10-GND-Pad3)") (class "Default")
      (node (ref "U10") (pin "3") (pinfunction "GND_3") (pintype "bidirectional"))
    )
  )
)
